# LEVER-board-production-0_SENT_to_OSHPark.net
KiCad netlist of a schematic drawn in EAGLE
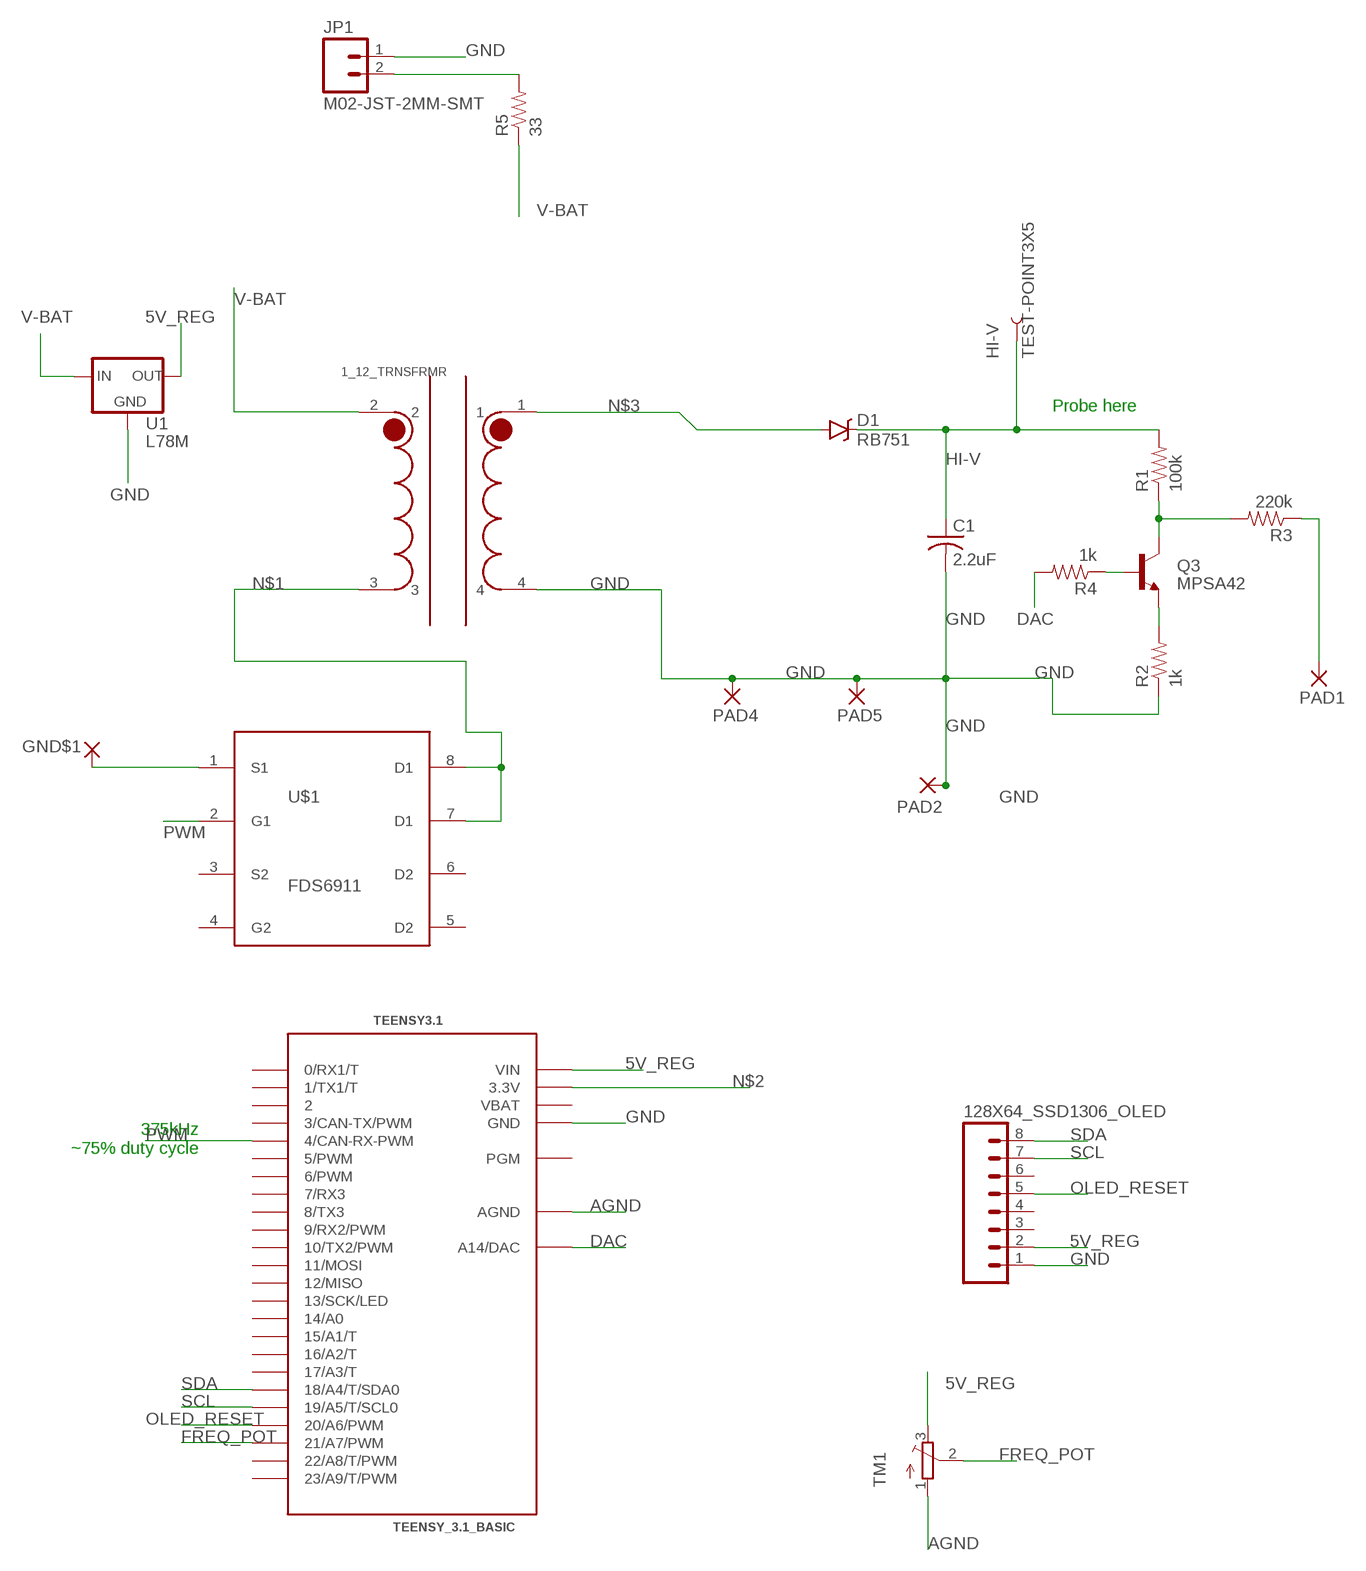
[diagram p0: schematic, sheet 1]

(export (version "E")
  (design (tool "Eeschema 10.0.6"))
  (components
    (comp (ref "1_12_TRNSFRMR")
      (value "PA0367")
      (footprint "eagle-import:PA0367")
      (libsource (lib "eagle-import") (part "PA0367"))
    )
    (comp (ref "128X64_SSD1306_OLED")
      (value "M08LOCK")
      (footprint "eagle-import:1X08_LOCK")
      (libsource (lib "eagle-import") (part "M08LOCK"))
    )
    (comp (ref "C1")
      (value "2.2uF")
      (footprint "eagle-import:C1812")
      (libsource (lib "eagle-import") (part "C-USC1812"))
    )
    (comp (ref "D1")
      (value "RB751")
      (footprint "eagle-import:TO263")
      (libsource (lib "eagle-import") (part "QH03BZ600"))
    )
    (comp (ref "GND$1")
      (value "WIREPADSMD5-2,5")
      (footprint "eagle-import:5-2,5")
      (libsource (lib "eagle-import") (part "WIREPADSMD5-2,5"))
    )
    (comp (ref "HI-V")
      (value "TEST-POINT3X5")
      (footprint "eagle-import:PAD.03X.05")
      (libsource (lib "eagle-import") (part "TEST-POINT3X5"))
    )
    (comp (ref "JP1")
      (value "M02-JST-2MM-SMT")
      (footprint "eagle-import:JST-2-SMD")
      (libsource (lib "eagle-import") (part "M02-JST-2MM-SMT"))
    )
    (comp (ref "PAD1")
      (value "WIREPADSMD5-2,5")
      (footprint "eagle-import:5-2,5")
      (libsource (lib "eagle-import") (part "WIREPADSMD5-2,5"))
    )
    (comp (ref "PAD2")
      (value "WIREPADSMD5-2,5")
      (footprint "eagle-import:5-2,5")
      (libsource (lib "eagle-import") (part "WIREPADSMD5-2,5"))
    )
    (comp (ref "PAD4")
      (value "WIREPADSMD5-2,5")
      (footprint "eagle-import:5-2,5")
      (libsource (lib "eagle-import") (part "WIREPADSMD5-2,5"))
    )
    (comp (ref "PAD5")
      (value "WIREPADSMD5-2,5")
      (footprint "eagle-import:5-2,5")
      (libsource (lib "eagle-import") (part "WIREPADSMD5-2,5"))
    )
    (comp (ref "Q3")
      (value "MPSA42")
      (footprint "eagle-import:TO-92")
      (libsource (lib "eagle-import") (part "TRANSISTOR_NPNP2N2222A"))
    )
    (comp (ref "R1")
      (value "100k")
      (footprint "eagle-import:R2010")
      (libsource (lib "eagle-import") (part "RESISTOR2010"))
    )
    (comp (ref "R2")
      (value "1k")
      (footprint "eagle-import:1206")
      (libsource (lib "eagle-import") (part "RESISTOR1206"))
    )
    (comp (ref "R3")
      (value "220k")
      (footprint "eagle-import:R2010")
      (libsource (lib "eagle-import") (part "RESISTOR2010"))
    )
    (comp (ref "R4")
      (value "1k")
      (footprint "eagle-import:1206")
      (libsource (lib "eagle-import") (part "RESISTOR1206"))
    )
    (comp (ref "R5")
      (value "33")
      (footprint "eagle-import:1206")
      (libsource (lib "eagle-import") (part "RESISTOR1206"))
    )
    (comp (ref "TEENSY3.1")
      (value "TEENSY_3.1_BASIC")
      (footprint "eagle-import:TEENSY_3.1_BASIC")
      (libsource (lib "eagle-import") (part "TEENSY_3.1_BASIC"))
    )
    (comp (ref "TM1")
      (value "TRIMPOT3386")
      (footprint "eagle-import:TRIM-3386")
      (libsource (lib "eagle-import") (part "TRIMPOT3386"))
    )
    (comp (ref "U$1")
      (value "FDS6911")
      (footprint "eagle-import:SO8")
      (libsource (lib "eagle-import") (part "FDS6911"))
    )
    (comp (ref "U1")
      (value "L78M")
      (footprint "eagle-import:DPAK")
      (libsource (lib "eagle-import") (part "L78M"))
    )
  )
  (nets
    (net (code "1") (name "/5V_REG") (class "Default")
      (node (ref "128X64_SSD1306_OLED") (pin "2") (pinfunction "2_2") (pintype "passive"))
      (node (ref "TEENSY3.1") (pin "VIN") (pinfunction "VIN_VIN") (pintype "power_in"))
      (node (ref "TM1") (pin "3") (pinfunction "E_3") (pintype "passive"))
      (node (ref "U1") (pin "3") (pinfunction "OUT_3") (pintype "passive"))
    )
    (net (code "2") (name "/AGND") (class "Default")
      (node (ref "TEENSY3.1") (pin "AGND") (pinfunction "AGND_AGND") (pintype "power_in"))
      (node (ref "TM1") (pin "1") (pinfunction "A_1") (pintype "passive"))
    )
    (net (code "3") (name "/DAC") (class "Default")
      (node (ref "R4") (pin "2") (pinfunction "2_2") (pintype "passive"))
      (node (ref "TEENSY3.1") (pin "A14") (pinfunction "A14/DAC_A14") (pintype "bidirectional"))
    )
    (net (code "4") (name "/FREQ_POT") (class "Default")
      (node (ref "TEENSY3.1") (pin "21/A7") (pinfunction "21/A7/PWM_21/A7") (pintype "bidirectional"))
      (node (ref "TM1") (pin "2") (pinfunction "S_2") (pintype "passive"))
    )
    (net (code "5") (name "/GND") (class "Default")
      (node (ref "128X64_SSD1306_OLED") (pin "1") (pinfunction "1_1") (pintype "passive"))
      (node (ref "1_12_TRNSFRMR") (pin "4") (pinfunction "4_4") (pintype "bidirectional"))
      (node (ref "C1") (pin "2") (pinfunction "2_2") (pintype "passive"))
      (node (ref "GND$1") (pin "1") (pinfunction "P_1") (pintype "passive"))
      (node (ref "JP1") (pin "1") (pinfunction "2_1") (pintype "passive"))
      (node (ref "PAD2") (pin "1") (pinfunction "P_1") (pintype "passive"))
      (node (ref "PAD4") (pin "1") (pinfunction "P_1") (pintype "passive"))
      (node (ref "PAD5") (pin "1") (pinfunction "P_1") (pintype "passive"))
      (node (ref "R2") (pin "1") (pinfunction "1_1") (pintype "passive"))
      (node (ref "TEENSY3.1") (pin "GND") (pinfunction "GND_GND") (pintype "power_in"))
      (node (ref "TEENSY3.1") (pin "GND1") (pinfunction "GND_GND1") (pintype "power_in"))
      (node (ref "U$1") (pin "1") (pinfunction "S1_1") (pintype "bidirectional"))
      (node (ref "U1") (pin "4") (pinfunction "GND_4") (pintype "input"))
    )
    (net (code "6") (name "/HI-V") (class "Default")
      (node (ref "C1") (pin "1") (pinfunction "1_1") (pintype "passive"))
      (node (ref "D1") (pin "1") (pinfunction "C_1") (pintype "passive"))
      (node (ref "HI-V") (pin "P$1") (pinfunction "1_P$1") (pintype "bidirectional"))
      (node (ref "R1") (pin "2") (pinfunction "2_2") (pintype "passive"))
    )
    (net (code "7") (name "/N$1") (class "Default")
      (node (ref "1_12_TRNSFRMR") (pin "3") (pinfunction "3_3") (pintype "bidirectional"))
      (node (ref "U$1") (pin "7") (pinfunction "D1_7") (pintype "bidirectional"))
      (node (ref "U$1") (pin "8") (pinfunction "D1_8") (pintype "bidirectional"))
    )
    (net (code "8") (name "/N$2") (class "Default")
      (node (ref "TEENSY3.1") (pin "3.3V") (pinfunction "3.3V_3.3V") (pintype "power_in"))
      (node (ref "TEENSY3.1") (pin "3.3V1") (pinfunction "3.3V_3.3V1") (pintype "power_in"))
    )
    (net (code "9") (name "/N$3") (class "Default")
      (node (ref "1_12_TRNSFRMR") (pin "1") (pinfunction "1_1") (pintype "bidirectional"))
      (node (ref "D1") (pin "2") (pinfunction "A_2") (pintype "passive"))
    )
    (net (code "10") (name "/OLED_RESET") (class "Default")
      (node (ref "128X64_SSD1306_OLED") (pin "5") (pinfunction "5_5") (pintype "passive"))
      (node (ref "TEENSY3.1") (pin "20/A6") (pinfunction "20/A6/PWM_20/A6") (pintype "bidirectional"))
    )
    (net (code "11") (name "/PWM") (class "Default")
      (node (ref "TEENSY3.1") (pin "4") (pinfunction "4/CAN-RX-PWM_4") (pintype "bidirectional"))
      (node (ref "U$1") (pin "2") (pinfunction "G1_2") (pintype "bidirectional"))
    )
    (net (code "12") (name "/SCL") (class "Default")
      (node (ref "128X64_SSD1306_OLED") (pin "7") (pinfunction "7_7") (pintype "passive"))
      (node (ref "TEENSY3.1") (pin "19/A5") (pinfunction "19/A5/T/SCL0_19/A5") (pintype "bidirectional"))
    )
    (net (code "13") (name "/SDA") (class "Default")
      (node (ref "128X64_SSD1306_OLED") (pin "8") (pinfunction "8_8") (pintype "passive"))
      (node (ref "TEENSY3.1") (pin "18/A4") (pinfunction "18/A4/T/SDA0_18/A4") (pintype "bidirectional"))
    )
    (net (code "14") (name "/V-BAT") (class "Default")
      (node (ref "1_12_TRNSFRMR") (pin "2") (pinfunction "2_2") (pintype "bidirectional"))
      (node (ref "R5") (pin "1") (pinfunction "1_1") (pintype "passive"))
      (node (ref "U1") (pin "1") (pinfunction "IN_1") (pintype "input"))
    )
    (net (code "15") (name "/VBAT") (class "Default")
      (node (ref "TEENSY3.1") (pin "VBAT") (pinfunction "VBAT_VBAT") (pintype "power_in"))
    )
    (net (code "16") (name "Net-(JP1-1)") (class "Default")
      (node (ref "JP1") (pin "2") (pinfunction "1_2") (pintype "passive"))
      (node (ref "R5") (pin "2") (pinfunction "2_2") (pintype "passive"))
    )
    (net (code "17") (name "Net-(PAD1-P)") (class "Default")
      (node (ref "PAD1") (pin "1") (pinfunction "P_1") (pintype "passive"))
      (node (ref "R3") (pin "1") (pinfunction "1_1") (pintype "passive"))
    )
    (net (code "18") (name "Net-(Q3-B)") (class "Default")
      (node (ref "Q3") (pin "2") (pinfunction "B_2") (pintype "passive"))
      (node (ref "R4") (pin "1") (pinfunction "1_1") (pintype "passive"))
    )
    (net (code "19") (name "Net-(Q3-C)") (class "Default")
      (node (ref "Q3") (pin "1") (pinfunction "C_1") (pintype "passive"))
      (node (ref "R1") (pin "1") (pinfunction "1_1") (pintype "passive"))
      (node (ref "R3") (pin "2") (pinfunction "2_2") (pintype "passive"))
    )
    (net (code "20") (name "Net-(Q3-E)") (class "Default")
      (node (ref "Q3") (pin "3") (pinfunction "E_3") (pintype "passive"))
      (node (ref "R2") (pin "2") (pinfunction "2_2") (pintype "passive"))
    )
    (net (code "21") (name "unconnected-(128X64_SSD1306_OLED-Pad3)") (class "Default")
      (node (ref "128X64_SSD1306_OLED") (pin "3") (pinfunction "3_3") (pintype "passive"))
    )
    (net (code "22") (name "unconnected-(128X64_SSD1306_OLED-Pad4)") (class "Default")
      (node (ref "128X64_SSD1306_OLED") (pin "4") (pinfunction "4_4") (pintype "passive"))
    )
    (net (code "23") (name "unconnected-(128X64_SSD1306_OLED-Pad6)") (class "Default")
      (node (ref "128X64_SSD1306_OLED") (pin "6") (pinfunction "6_6") (pintype "passive"))
    )
    (net (code "24") (name "unconnected-(TEENSY3.1-0{slash}RX1{slash}T-Pad0)") (class "Default")
      (node (ref "TEENSY3.1") (pin "0") (pinfunction "0/RX1/T_0") (pintype "bidirectional"))
    )
    (net (code "25") (name "unconnected-(TEENSY3.1-1{slash}TX1{slash}T-Pad1)") (class "Default")
      (node (ref "TEENSY3.1") (pin "1") (pinfunction "1/TX1/T_1") (pintype "bidirectional"))
    )
    (net (code "26") (name "unconnected-(TEENSY3.1-3{slash}CAN-TX{slash}PWM-Pad3)") (class "Default")
      (node (ref "TEENSY3.1") (pin "3") (pinfunction "3/CAN-TX/PWM_3") (pintype "bidirectional"))
    )
    (net (code "27") (name "unconnected-(TEENSY3.1-5{slash}PWM-Pad5)") (class "Default")
      (node (ref "TEENSY3.1") (pin "5") (pinfunction "5/PWM_5") (pintype "bidirectional"))
    )
    (net (code "28") (name "unconnected-(TEENSY3.1-6{slash}PWM-Pad6)") (class "Default")
      (node (ref "TEENSY3.1") (pin "6") (pinfunction "6/PWM_6") (pintype "bidirectional"))
    )
    (net (code "29") (name "unconnected-(TEENSY3.1-7{slash}RX3-Pad7)") (class "Default")
      (node (ref "TEENSY3.1") (pin "7") (pinfunction "7/RX3_7") (pintype "bidirectional"))
    )
    (net (code "30") (name "unconnected-(TEENSY3.1-8{slash}TX3-Pad8)") (class "Default")
      (node (ref "TEENSY3.1") (pin "8") (pinfunction "8/TX3_8") (pintype "bidirectional"))
    )
    (net (code "31") (name "unconnected-(TEENSY3.1-9{slash}RX2{slash}PWM-Pad9)") (class "Default")
      (node (ref "TEENSY3.1") (pin "9") (pinfunction "9/RX2/PWM_9") (pintype "bidirectional"))
    )
    (net (code "32") (name "unconnected-(TEENSY3.1-10{slash}TX2{slash}PWM-Pad10)") (class "Default")
      (node (ref "TEENSY3.1") (pin "10") (pinfunction "10/TX2/PWM_10") (pintype "bidirectional"))
    )
    (net (code "33") (name "unconnected-(TEENSY3.1-11{slash}MOSI-Pad11)") (class "Default")
      (node (ref "TEENSY3.1") (pin "11") (pinfunction "11/MOSI_11") (pintype "bidirectional"))
    )
    (net (code "34") (name "unconnected-(TEENSY3.1-12{slash}MISO-Pad12)") (class "Default")
      (node (ref "TEENSY3.1") (pin "12") (pinfunction "12/MISO_12") (pintype "bidirectional"))
    )
    (net (code "35") (name "unconnected-(TEENSY3.1-13{slash}SCK{slash}LED-Pad13)") (class "Default")
      (node (ref "TEENSY3.1") (pin "13") (pinfunction "13/SCK/LED_13") (pintype "bidirectional"))
    )
    (net (code "36") (name "unconnected-(TEENSY3.1-15{slash}A1{slash}T-Pad15{slash}A1)") (class "Default")
      (node (ref "TEENSY3.1") (pin "15/A1") (pinfunction "15/A1/T_15/A1") (pintype "bidirectional"))
    )
    (net (code "37") (name "unconnected-(TEENSY3.1-16{slash}A2{slash}T-Pad16{slash}A2)") (class "Default")
      (node (ref "TEENSY3.1") (pin "16/A2") (pinfunction "16/A2/T_16/A2") (pintype "bidirectional"))
    )
    (net (code "38") (name "unconnected-(TEENSY3.1-17{slash}A3{slash}T-Pad17{slash}A3)") (class "Default")
      (node (ref "TEENSY3.1") (pin "17/A3") (pinfunction "17/A3/T_17/A3") (pintype "bidirectional"))
    )
    (net (code "39") (name "unconnected-(TEENSY3.1-22{slash}A8{slash}T{slash}PWM-Pad22{slash}A8)") (class "Default")
      (node (ref "TEENSY3.1") (pin "22/A8") (pinfunction "22/A8/T/PWM_22/A8") (pintype "bidirectional"))
    )
    (net (code "40") (name "unconnected-(TEENSY3.1-23{slash}A9{slash}T{slash}PWM-Pad23{slash}A9)") (class "Default")
      (node (ref "TEENSY3.1") (pin "23/A9") (pinfunction "23/A9/T/PWM_23/A9") (pintype "bidirectional"))
    )
    (net (code "41") (name "unconnected-(TEENSY3.1-Pad2)") (class "Default")
      (node (ref "TEENSY3.1") (pin "2") (pinfunction "2_2") (pintype "bidirectional"))
    )
    (net (code "42") (name "unconnected-(TEENSY3.1-Pad14{slash}A0)") (class "Default")
      (node (ref "TEENSY3.1") (pin "14/A0") (pinfunction "14/A0_14/A0") (pintype "bidirectional"))
    )
    (net (code "43") (name "unconnected-(TEENSY3.1-PadPGM)") (class "Default")
      (node (ref "TEENSY3.1") (pin "PGM") (pinfunction "PGM_PGM") (pintype "bidirectional"))
    )
    (net (code "44") (name "unconnected-(U$1-D2-Pad5)") (class "Default")
      (node (ref "U$1") (pin "5") (pinfunction "D2_5") (pintype "bidirectional"))
    )
    (net (code "45") (name "unconnected-(U$1-D2-Pad6)") (class "Default")
      (node (ref "U$1") (pin "6") (pinfunction "D2_6") (pintype "bidirectional"))
    )
    (net (code "46") (name "unconnected-(U$1-G2-Pad4)") (class "Default")
      (node (ref "U$1") (pin "4") (pinfunction "G2_4") (pintype "bidirectional"))
    )
    (net (code "47") (name "unconnected-(U$1-S2-Pad3)") (class "Default")
      (node (ref "U$1") (pin "3") (pinfunction "S2_3") (pintype "bidirectional"))
    )
  )
)
